# SCH_V1.net
KiCad netlist of a schematic drawn in Altium Designer
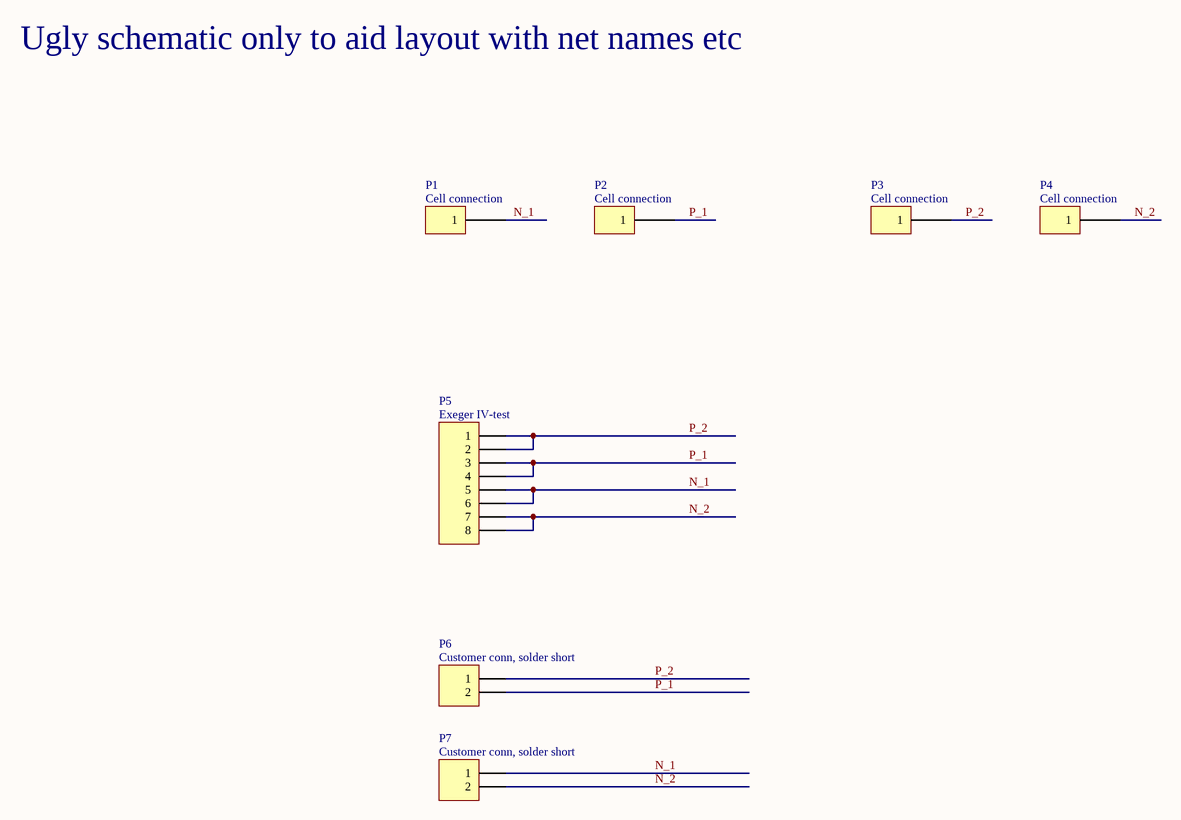
[diagram p0: SCH_V1.SchDoc]

(export (version "E")
  (design (tool "Eeschema 10.0.6"))
  (components
    (comp (ref "P1")
      (value "Cell connection")
      (footprint "Cell_Pad_4mm")
      (libsource (lib "Flex_SCH_symbols") (part "Cell connection 1P"))
    )
    (comp (ref "P2")
      (value "Cell connection")
      (footprint "Cell_Pad_4mm")
      (libsource (lib "Flex_SCH_symbols") (part "Cell connection 1P"))
    )
    (comp (ref "P3")
      (value "Cell connection")
      (footprint "Cell_Pad_4mm")
      (libsource (lib "Flex_SCH_symbols") (part "Cell connection 1P"))
    )
    (comp (ref "P4")
      (value "Cell connection")
      (footprint "Cell_Pad_4mm")
      (libsource (lib "Flex_SCH_symbols") (part "Cell connection 1P"))
    )
    (comp (ref "P5")
      (value "Exeger IV-test")
      (footprint "EXEGER_IV_8_PIN_NO_STIFF")
      (description "Header, 8-Pin")
      (libsource (lib "Miscellaneous Connectors") (part "Header 8"))
    )
    (comp (ref "P6")
      (value "Customer conn, solder short")
      (footprint "Customer_2022_solder_short")
      (description "Header, 2-Pin")
      (libsource (lib "Miscellaneous Connectors") (part "Header 2"))
    )
    (comp (ref "P7")
      (value "Customer conn, solder short")
      (footprint "Customer_2022_solder_short")
      (description "Header, 2-Pin")
      (libsource (lib "Miscellaneous Connectors") (part "Header 2"))
    )
  )
  (nets
    (net (code "1") (name "/N_1") (class "Default")
      (node (ref "P1") (pin "1") (pinfunction "1_1") (pintype "passive"))
      (node (ref "P5") (pin "5") (pinfunction "5_5") (pintype "passive"))
      (node (ref "P5") (pin "6") (pinfunction "6_6") (pintype "passive"))
      (node (ref "P7") (pin "1") (pinfunction "1_1") (pintype "passive"))
    )
    (net (code "2") (name "/N_2") (class "Default")
      (node (ref "P4") (pin "1") (pinfunction "1_1") (pintype "passive"))
      (node (ref "P5") (pin "7") (pinfunction "7_7") (pintype "passive"))
      (node (ref "P5") (pin "8") (pinfunction "8_8") (pintype "passive"))
      (node (ref "P7") (pin "2") (pinfunction "2_2") (pintype "passive"))
    )
    (net (code "3") (name "/P_1") (class "Default")
      (node (ref "P2") (pin "1") (pinfunction "1_1") (pintype "passive"))
      (node (ref "P5") (pin "3") (pinfunction "3_3") (pintype "passive"))
      (node (ref "P5") (pin "4") (pinfunction "4_4") (pintype "passive"))
      (node (ref "P6") (pin "2") (pinfunction "2_2") (pintype "passive"))
    )
    (net (code "4") (name "/P_2") (class "Default")
      (node (ref "P3") (pin "1") (pinfunction "1_1") (pintype "passive"))
      (node (ref "P5") (pin "1") (pinfunction "1_1") (pintype "passive"))
      (node (ref "P5") (pin "2") (pinfunction "2_2") (pintype "passive"))
      (node (ref "P6") (pin "1") (pinfunction "1_1") (pintype "passive"))
    )
  )
)
